# Input_Power.net
KiCad netlist of a schematic drawn in Altium Designer
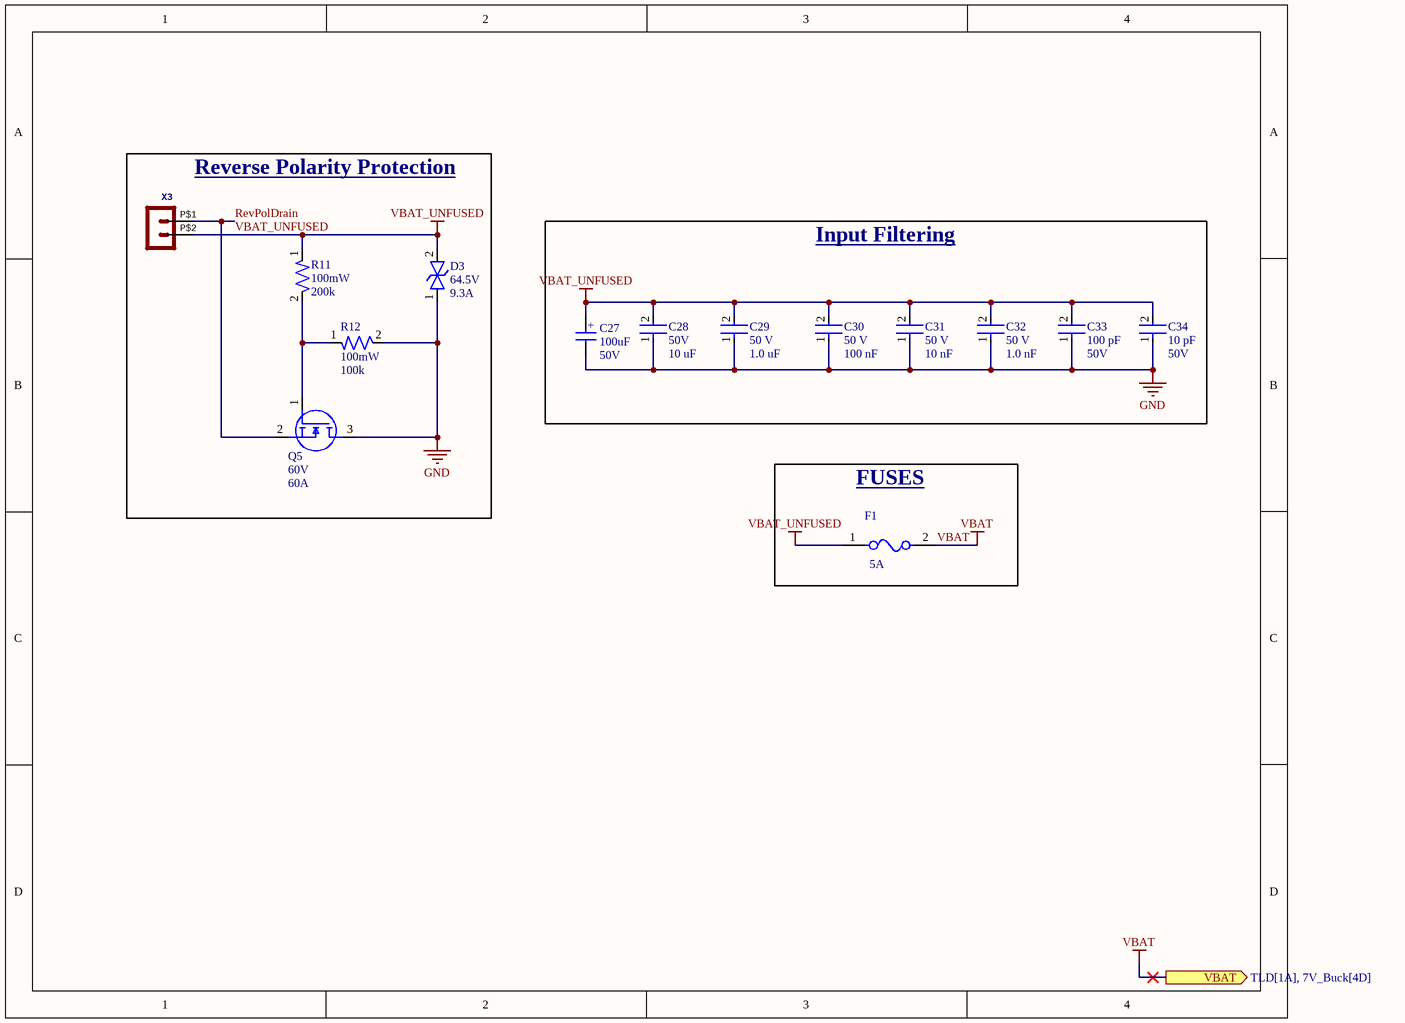
[diagram p0: Input_Power.SchDoc]

(export (version "E")
  (design (tool "Eeschema 10.0.6"))
  (components
    (comp (ref "C27")
      (value "860040674004")
      (footprint "WCAP-ATUL_8X11.5(DXL)")
      (description "100 µF 50 V Aluminum Electrolytic Capacitors Radial, Can 7000 Hrs @ 105°C")
      (fields
        (field (name "MF") "{'manufacturer': u'~{W}xfcrth Elektronik'}")
        (field (name "CAPACITANCE") "100uF")
        (field (name "VOLTAGE") "50V")
      )
      (libsource (lib "JLC_25") (part "CAP-100U-0002_1"))
    )
    (comp (ref "C28")
      (value "CL32B106KBJNNNE")
      (footprint "CAP-1210")
      (description "CAP CER 10UF 50V X7R 1210")
      (fields (field (name "VOLTAGE") "50V") (field (name "CAPACITANCE") "10 uF"))
      (libsource (lib "JLC_25") (part "CAP-10U-0002"))
    )
    (comp (ref "C29")
      (value "CC0805KKX7R9BB105")
      (footprint "CAP-0805")
      (description "CAP CER 1UF 50V X7R 0805")
      (fields (field (name "VOLTAGE") "50 V") (field (name "CAPACITANCE") "1.0 uF"))
      (libsource (lib "JLC_25") (part "CAP-1U-0001"))
    )
    (comp (ref "C30")
      (value "CC0805KRX7R9BB104")
      (footprint "CAP-0805")
      (description "CAP CER 0.1UF 50V X7R 0805")
      (fields (field (name "VOLTAGE RATING") "50 V") (field (name "CAPACITANCE") "100 nF"))
      (libsource (lib "JLC_25") (part "CAP-0.1U-0002"))
    )
    (comp (ref "C31")
      (value "CC0603KPX7R9BB103")
      (footprint "CAP-0603")
      (description "CAP CER 10000PF 50V X7R 0603")
      (fields (field (name "VOLTAGE") "50 V") (field (name "CAPACITANCE") "10 nF"))
      (libsource (lib "JLC_25") (part "CAP-10N-0002"))
    )
    (comp (ref "C32")
      (value "CC0402KRX7R9BB102")
      (footprint "CAP-0402")
      (description "CAP CER 1000PF 50V X7R 0402")
      (fields (field (name "VOLTAGE") "50 V") (field (name "CAPACITANCE") "1.0 nF"))
      (libsource (lib "JLC_25") (part "CAP-1N-0001"))
    )
    (comp (ref "C33")
      (value "CC0402JRNPO9BN101")
      (footprint "CAP-0402")
      (description "CAP CER 100PF 50V C0G/NPO 0402")
      (fields (field (name "CAPACITANCE") "100 pF") (field (name "VOLTAGE") "50V"))
      (libsource (lib "JLC_25") (part "CAP-100P-0001"))
    )
    (comp (ref "C34")
      (value "CC0402JRNPO9BN100")
      (footprint "CAP-0402")
      (description "CAP CER 10PF 50V C0G/NPO 0402")
      (fields (field (name "CAPACITANCE") "10 pF") (field (name "VOLTAGE") "50V"))
      (libsource (lib "JLC_25") (part "CAP-10P-0001"))
    )
    (comp (ref "D3")
      (value "SMBJ40CA")
      (footprint "DO-214AA (SMBJ)")
      (description "TVS DIODE 40VWM 64.5VC DO214AA")
      (fields (field (name "VOLTAGE RATING") "64.5V") (field (name "CURRENT RATING") "9.3A"))
      (libsource (lib "JLC_25") (part "DIO-TVS-0001"))
    )
    (comp (ref "F1")
      (value "01550900M")
      (footprint "FUSE-0001")
      (description "FUSE BLOK CARTRIDGE 125V 10A SMD")
      (fields (field (name "FUSE CURRENT") "5A"))
      (libsource (lib "JLC_25") (part "FUSE-0001"))
    )
    (comp (ref "Q5")
      (value "CSD18543Q3AT")
      (footprint "IC-8VSONCLIP")
      (description "MOSFET N-CH 60V 12A/60A 8VSON")
      (fields (field (name "VOLTAGE") "60V") (field (name "CONTINUOUS CURRENT") "60A"))
      (libsource (lib "JLC_25") (part "NMOS-60A-0001"))
    )
    (comp (ref "R11")
      (value "RC0603FR-07200KL")
      (footprint "RES-0603")
      (description "RES SMD 200K OHM 1% 1/10W 0603")
      (fields
        (field (name "TOLERANCE") "1%")
        (field (name "POWER") "100mW")
        (field (name "RESISTANCE") "200k")
      )
      (libsource (lib "JLC_25") (part "RES-200k-0001"))
    )
    (comp (ref "R12")
      (value "RC0603FR-07100KL")
      (footprint "RES-0603")
      (description "RES SMD 100K OHM 1% 1/10W 0603")
      (fields
        (field (name "TOLERANCE") "1%")
        (field (name "POWER") "100mW")
        (field (name "RESISTANCE") "100k")
      )
      (libsource (lib "JLC_25") (part "RES-100k-0001"))
    )
    (comp (ref "X3")
      (value "Molex - Micro-Fit 3.0 Series connector,  3.00mm (0.118\") pitch header, 2 positions.")
      (footprint "43045-0200")
      (libsource (lib "Molex Microfit") (part "HEADER_POS2_?43045-0200"))
    )
  )
  (nets
    (net (code "1") (name "/RevPolDrain") (class "Default")
      (node (ref "Q5") (pin "2") (pinfunction "S_2") (pintype "passive"))
      (node (ref "X3") (pin "P$1") (pinfunction "1_P$1") (pintype "passive"))
    )
    (net (code "2") (name "GND") (class "Default")
      (node (ref "C27") (pin "2") (pinfunction "NEG_2") (pintype "passive"))
      (node (ref "C28") (pin "1") (pinfunction "1_1") (pintype "passive"))
      (node (ref "C29") (pin "1") (pinfunction "1_1") (pintype "passive"))
      (node (ref "C30") (pin "1") (pinfunction "1_1") (pintype "passive"))
      (node (ref "C31") (pin "1") (pinfunction "1_1") (pintype "passive"))
      (node (ref "C32") (pin "1") (pinfunction "1_1") (pintype "passive"))
      (node (ref "C33") (pin "1") (pinfunction "1_1") (pintype "passive"))
      (node (ref "C34") (pin "1") (pinfunction "1_1") (pintype "passive"))
      (node (ref "D3") (pin "1") (pintype "passive"))
      (node (ref "Q5") (pin "3") (pinfunction "D_3") (pintype "passive"))
      (node (ref "R12") (pin "2") (pinfunction "2_2") (pintype "passive"))
    )
    (net (code "3") (name "Net-(Q5-G)") (class "Default")
      (node (ref "Q5") (pin "1") (pinfunction "G_1") (pintype "passive"))
      (node (ref "R11") (pin "2") (pinfunction "2_2") (pintype "passive"))
      (node (ref "R12") (pin "1") (pinfunction "1_1") (pintype "passive"))
    )
    (net (code "4") (name "VBAT") (class "Default")
      (node (ref "F1") (pin "2") (pinfunction "2_2") (pintype "passive"))
    )
    (net (code "5") (name "VBAT_UNFUSED") (class "Default")
      (node (ref "C27") (pin "1") (pinfunction "POS_1") (pintype "passive"))
      (node (ref "C28") (pin "2") (pinfunction "2_2") (pintype "passive"))
      (node (ref "C29") (pin "2") (pinfunction "2_2") (pintype "passive"))
      (node (ref "C30") (pin "2") (pinfunction "2_2") (pintype "passive"))
      (node (ref "C31") (pin "2") (pinfunction "2_2") (pintype "passive"))
      (node (ref "C32") (pin "2") (pinfunction "2_2") (pintype "passive"))
      (node (ref "C33") (pin "2") (pinfunction "2_2") (pintype "passive"))
      (node (ref "C34") (pin "2") (pinfunction "2_2") (pintype "passive"))
      (node (ref "D3") (pin "2") (pintype "passive"))
      (node (ref "F1") (pin "1") (pinfunction "1_1") (pintype "passive"))
      (node (ref "R11") (pin "1") (pinfunction "1_1") (pintype "passive"))
      (node (ref "X3") (pin "P$2") (pinfunction "2_P$2") (pintype "passive"))
    )
  )
)
